# ClockRecovery.net
KiCad netlist of a schematic drawn in Altium Designer
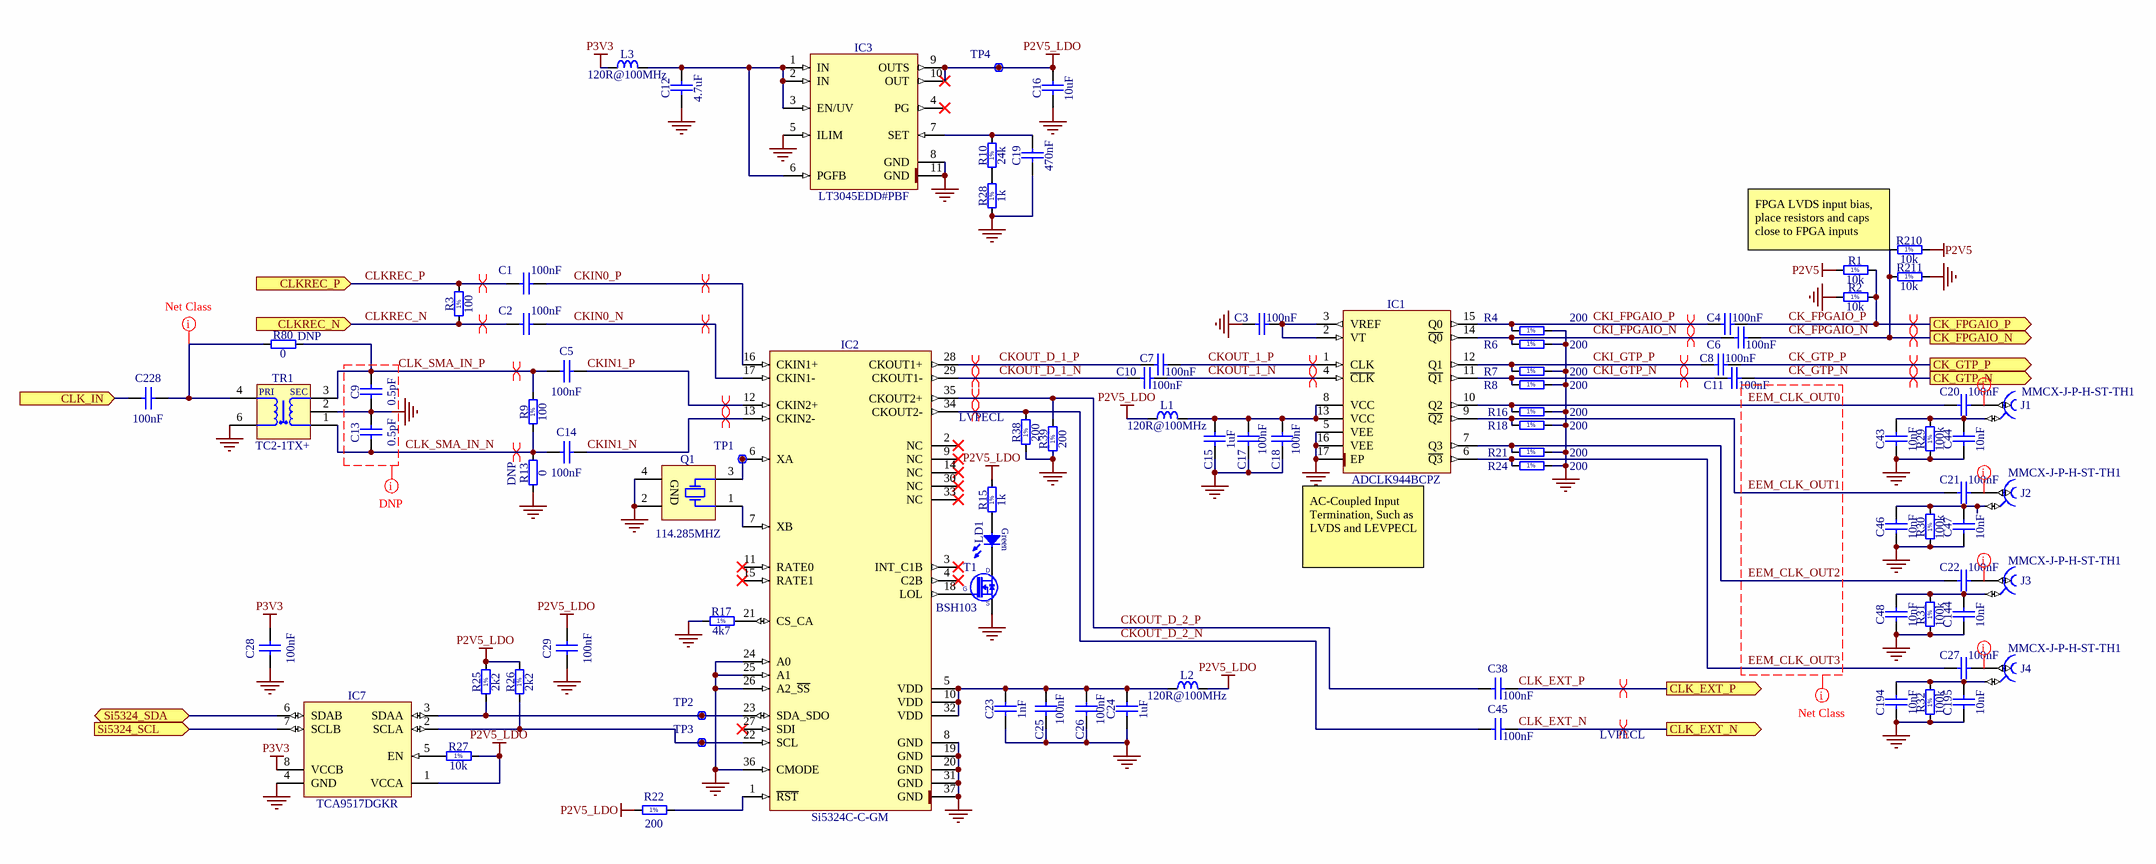
[diagram p0: ClockRecovery.SchDoc]

(export (version "E")
  (design (tool "Eeschema 10.0.6"))
  (components
    (comp (ref "C1")
      (value "100nF")
      (footprint "CAPC0603X33N")
      (description "Non-polarised capacitor")
      (fields
        (field (name "PART NUMBER") "CC0201_100NF_6.3V_10%_X5R")
        (field (name "VOLTAGE") "6.3V")
        (field (name "AUTHOR") "CERN DEM JLC")
      )
      (libsource (lib "Capacitors") (part "Capacitor - non polarized"))
    )
    (comp (ref "C2")
      (value "100nF")
      (footprint "CAPC0603X33N")
      (description "Non-polarised capacitor")
      (fields
        (field (name "PART NUMBER") "CC0201_100NF_6.3V_10%_X5R")
        (field (name "VOLTAGE") "6.3V")
        (field (name "AUTHOR") "CERN DEM JLC")
      )
      (libsource (lib "Capacitors") (part "Capacitor - non polarized"))
    )
    (comp (ref "C3")
      (value "100nF")
      (footprint "CAPC0603X33N")
      (description "Non-polarised capacitor")
      (fields
        (field (name "PART NUMBER") "CC0201_100NF_6.3V_10%_X5R")
        (field (name "VOLTAGE") "6.3V")
        (field (name "AUTHOR") "CERN DEM JLC")
      )
      (libsource (lib "Capacitors") (part "Capacitor - non polarized"))
    )
    (comp (ref "C4")
      (value "100nF")
      (footprint "CAPC0603X33N")
      (description "Non-polarised capacitor")
      (fields
        (field (name "PART NUMBER") "CC0201_100NF_6.3V_10%_X5R")
        (field (name "VOLTAGE") "6.3V")
        (field (name "AUTHOR") "CERN DEM JLC")
      )
      (libsource (lib "Capacitors") (part "Capacitor - non polarized"))
    )
    (comp (ref "C5")
      (value "100nF")
      (footprint "CAPC0603X33N")
      (description "Non-polarised capacitor")
      (fields
        (field (name "PART NUMBER") "CC0201_100NF_6.3V_10%_X5R")
        (field (name "VOLTAGE") "6.3V")
        (field (name "AUTHOR") "CERN DEM JLC")
      )
      (libsource (lib "Capacitors") (part "Capacitor - non polarized"))
    )
    (comp (ref "C6")
      (value "100nF")
      (footprint "CAPC0603X33N")
      (description "Non-polarised capacitor")
      (fields
        (field (name "PART NUMBER") "CC0201_100NF_6.3V_10%_X5R")
        (field (name "VOLTAGE") "6.3V")
        (field (name "AUTHOR") "CERN DEM JLC")
      )
      (libsource (lib "Capacitors") (part "Capacitor - non polarized"))
    )
    (comp (ref "C7")
      (value "100nF")
      (footprint "CAPC0603X33N")
      (description "Non-polarised capacitor")
      (fields
        (field (name "PART NUMBER") "CC0201_100NF_6.3V_10%_X5R")
        (field (name "VOLTAGE") "6.3V")
        (field (name "AUTHOR") "CERN DEM JLC")
      )
      (libsource (lib "Capacitors") (part "Capacitor - non polarized"))
    )
    (comp (ref "C8")
      (value "100nF")
      (footprint "CAPC0603X33N")
      (description "Non-polarised capacitor")
      (fields
        (field (name "PART NUMBER") "CC0201_100NF_6.3V_10%_X5R")
        (field (name "VOLTAGE") "6.3V")
        (field (name "AUTHOR") "CERN DEM JLC")
      )
      (libsource (lib "Capacitors") (part "Capacitor - non polarized"))
    )
    (comp (ref "C9")
      (value "0.5pF")
      (footprint "CAPC1005X50N")
      (description "Non-polarised capacitor")
      (fields
        (field (name "PART NUMBER") "CC0402_0.5PF_25V_0.05PF_AVX_04023J0R5ABSTR")
        (field (name "VOLTAGE") "25V")
        (field (name "AUTHOR") "CERN DEM JLC")
      )
      (libsource (lib "Capacitors") (part "Capacitor - non polarized"))
    )
    (comp (ref "C10")
      (value "100nF")
      (footprint "CAPC0603X33N")
      (description "Non-polarised capacitor")
      (fields
        (field (name "PART NUMBER") "CC0201_100NF_6.3V_10%_X5R")
        (field (name "VOLTAGE") "6.3V")
        (field (name "AUTHOR") "CERN DEM JLC")
      )
      (libsource (lib "Capacitors") (part "Capacitor - non polarized"))
    )
    (comp (ref "C11")
      (value "100nF")
      (footprint "CAPC0603X33N")
      (description "Non-polarised capacitor")
      (fields
        (field (name "PART NUMBER") "CC0201_100NF_6.3V_10%_X5R")
        (field (name "VOLTAGE") "6.3V")
        (field (name "AUTHOR") "CERN DEM JLC")
      )
      (libsource (lib "Capacitors") (part "Capacitor - non polarized"))
    )
    (comp (ref "C12")
      (value "4.7uF")
      (footprint "CAPC1005X55N")
      (description "Non-polarised capacitor")
      (fields
        (field (name "PART NUMBER") "CC0402_4.7UF_6.3V_20%_X5R")
        (field (name "VOLTAGE") "6.3V")
        (field (name "AUTHOR") "CERN DEM JLC")
      )
      (libsource (lib "Capacitors") (part "Capacitor - non polarized"))
    )
    (comp (ref "C13")
      (value "0.5pF")
      (footprint "CAPC1005X50N")
      (description "Non-polarised capacitor")
      (fields
        (field (name "PART NUMBER") "CC0402_0.5PF_25V_0.05PF_AVX_04023J0R5ABSTR")
        (field (name "VOLTAGE") "25V")
        (field (name "AUTHOR") "CERN DEM JLC")
      )
      (libsource (lib "Capacitors") (part "Capacitor - non polarized"))
    )
    (comp (ref "C14")
      (value "100nF")
      (footprint "CAPC0603X33N")
      (description "Non-polarised capacitor")
      (fields
        (field (name "PART NUMBER") "CC0201_100NF_6.3V_10%_X5R")
        (field (name "VOLTAGE") "6.3V")
        (field (name "AUTHOR") "CERN DEM JLC")
      )
      (libsource (lib "Capacitors") (part "Capacitor - non polarized"))
    )
    (comp (ref "C15")
      (value "1uF")
      (footprint "CAPC1005X55N")
      (description "Non-polarised capacitor")
      (fields
        (field (name "PART NUMBER") "CC0402_1UF_16V_10%_X5R")
        (field (name "VOLTAGE") "16V")
        (field (name "AUTHOR") "CERN DEM JLC")
      )
      (libsource (lib "Capacitors") (part "Capacitor - non polarized"))
    )
    (comp (ref "C16")
      (value "10uF")
      (footprint "CAPC1005X70N")
      (description "Non-polarised capacitor")
      (fields
        (field (name "PART NUMBER") "CC0402_10UF_6.3V_20%_X5R")
        (field (name "VOLTAGE") "6.3V")
        (field (name "AUTHOR") "CERN DEM JLC")
      )
      (libsource (lib "Capacitors") (part "Capacitor - non polarized"))
    )
    (comp (ref "C17")
      (value "100nF")
      (footprint "CAPC0603X33N")
      (description "Non-polarised capacitor")
      (fields
        (field (name "PART NUMBER") "CC0201_100NF_6.3V_10%_X5R")
        (field (name "VOLTAGE") "6.3V")
        (field (name "AUTHOR") "CERN DEM JLC")
      )
      (libsource (lib "Capacitors") (part "Capacitor - non polarized"))
    )
    (comp (ref "C18")
      (value "100nF")
      (footprint "CAPC0603X33N")
      (description "Non-polarised capacitor")
      (fields
        (field (name "PART NUMBER") "CC0201_100NF_6.3V_10%_X5R")
        (field (name "VOLTAGE") "6.3V")
        (field (name "AUTHOR") "CERN DEM JLC")
      )
      (libsource (lib "Capacitors") (part "Capacitor - non polarized"))
    )
    (comp (ref "C19")
      (value "470nF")
      (footprint "CAPC1005X55N")
      (description "Non-polarised capacitor")
      (fields
        (field (name "PART NUMBER") "CC0402_470NF_6.3V_10%_X5R")
        (field (name "VOLTAGE") "6.3V")
        (field (name "AUTHOR") "CERN DEM JLC")
      )
      (libsource (lib "Capacitors") (part "Capacitor - non polarized"))
    )
    (comp (ref "C20")
      (value "100nF")
      (footprint "CAPC0603X33N")
      (description "Non-polarised capacitor")
      (fields
        (field (name "PART NUMBER") "CC0201_100NF_6.3V_10%_X5R")
        (field (name "VOLTAGE") "6.3V")
        (field (name "AUTHOR") "CERN DEM JLC")
      )
      (libsource (lib "Capacitors") (part "Capacitor - non polarized"))
    )
    (comp (ref "C21")
      (value "100nF")
      (footprint "CAPC0603X33N")
      (description "Non-polarised capacitor")
      (fields
        (field (name "PART NUMBER") "CC0201_100NF_6.3V_10%_X5R")
        (field (name "VOLTAGE") "6.3V")
        (field (name "AUTHOR") "CERN DEM JLC")
      )
      (libsource (lib "Capacitors") (part "Capacitor - non polarized"))
    )
    (comp (ref "C22")
      (value "100nF")
      (footprint "CAPC0603X33N")
      (description "Non-polarised capacitor")
      (fields
        (field (name "PART NUMBER") "CC0201_100NF_6.3V_10%_X5R")
        (field (name "VOLTAGE") "6.3V")
        (field (name "AUTHOR") "CERN DEM JLC")
      )
      (libsource (lib "Capacitors") (part "Capacitor - non polarized"))
    )
    (comp (ref "C23")
      (value "1nF")
      (footprint "CAPC1005X55N")
      (description "Non-polarised capacitor")
      (fields
        (field (name "PART NUMBER") "CC0402_1NF_50V_10%_X7R")
        (field (name "VOLTAGE") "50V")
        (field (name "AUTHOR") "CERN DEM JLC")
      )
      (libsource (lib "Capacitors") (part "Capacitor - non polarized"))
    )
    (comp (ref "C24")
      (value "1uF")
      (footprint "CAPC1005X55N")
      (description "Non-polarised capacitor")
      (fields
        (field (name "PART NUMBER") "CC0402_1UF_16V_10%_X5R")
        (field (name "VOLTAGE") "16V")
        (field (name "AUTHOR") "CERN DEM JLC")
      )
      (libsource (lib "Capacitors") (part "Capacitor - non polarized"))
    )
    (comp (ref "C25")
      (value "100nF")
      (footprint "CAPC0603X33N")
      (description "Non-polarised capacitor")
      (fields
        (field (name "PART NUMBER") "CC0201_100NF_6.3V_10%_X5R")
        (field (name "VOLTAGE") "6.3V")
        (field (name "AUTHOR") "CERN DEM JLC")
      )
      (libsource (lib "Capacitors") (part "Capacitor - non polarized"))
    )
    (comp (ref "C26")
      (value "100nF")
      (footprint "CAPC0603X33N")
      (description "Non-polarised capacitor")
      (fields
        (field (name "PART NUMBER") "CC0201_100NF_6.3V_10%_X5R")
        (field (name "VOLTAGE") "6.3V")
        (field (name "AUTHOR") "CERN DEM JLC")
      )
      (libsource (lib "Capacitors") (part "Capacitor - non polarized"))
    )
    (comp (ref "C27")
      (value "100nF")
      (footprint "CAPC0603X33N")
      (description "Non-polarised capacitor")
      (fields
        (field (name "PART NUMBER") "CC0201_100NF_6.3V_10%_X5R")
        (field (name "VOLTAGE") "6.3V")
        (field (name "AUTHOR") "CERN DEM JLC")
      )
      (libsource (lib "Capacitors") (part "Capacitor - non polarized"))
    )
    (comp (ref "C28")
      (value "100nF")
      (footprint "CAPC0603X33N")
      (description "Non-polarised capacitor")
      (fields
        (field (name "PART NUMBER") "CC0201_100NF_6.3V_10%_X5R")
        (field (name "VOLTAGE") "6.3V")
        (field (name "AUTHOR") "CERN DEM JLC")
      )
      (libsource (lib "Capacitors") (part "Capacitor - non polarized"))
    )
    (comp (ref "C29")
      (value "100nF")
      (footprint "CAPC0603X33N")
      (description "Non-polarised capacitor")
      (fields
        (field (name "PART NUMBER") "CC0201_100NF_6.3V_10%_X5R")
        (field (name "VOLTAGE") "6.3V")
        (field (name "AUTHOR") "CERN DEM JLC")
      )
      (libsource (lib "Capacitors") (part "Capacitor - non polarized"))
    )
    (comp (ref "C38")
      (value "100nF")
      (footprint "CAPC0603X33N")
      (description "Non-polarised capacitor")
      (fields
        (field (name "PART NUMBER") "CC0201_100NF_6.3V_10%_X5R")
        (field (name "VOLTAGE") "6.3V")
        (field (name "AUTHOR") "CERN DEM JLC")
      )
      (libsource (lib "Capacitors") (part "Capacitor - non polarized"))
    )
    (comp (ref "C43")
      (value "10nF")
      (footprint "CAPC1005X55N")
      (description "Non-polarised capacitor")
      (fields
        (field (name "PART NUMBER") "CC0402_10NF_16V_10%_X7R")
        (field (name "VOLTAGE") "16V")
        (field (name "AUTHOR") "CERN DEM JLC")
      )
      (libsource (lib "Capacitors") (part "Capacitor - non polarized"))
    )
    (comp (ref "C44")
      (value "10nF")
      (footprint "CAPC1005X55N")
      (description "Non-polarised capacitor")
      (fields
        (field (name "PART NUMBER") "CC0402_10NF_16V_10%_X7R")
        (field (name "VOLTAGE") "16V")
        (field (name "AUTHOR") "CERN DEM JLC")
      )
      (libsource (lib "Capacitors") (part "Capacitor - non polarized"))
    )
    (comp (ref "C45")
      (value "100nF")
      (footprint "CAPC0603X33N")
      (description "Non-polarised capacitor")
      (fields
        (field (name "PART NUMBER") "CC0201_100NF_6.3V_10%_X5R")
        (field (name "VOLTAGE") "6.3V")
        (field (name "AUTHOR") "CERN DEM JLC")
      )
      (libsource (lib "Capacitors") (part "Capacitor - non polarized"))
    )
    (comp (ref "C46")
      (value "10nF")
      (footprint "CAPC1005X55N")
      (description "Non-polarised capacitor")
      (fields
        (field (name "PART NUMBER") "CC0402_10NF_16V_10%_X7R")
        (field (name "VOLTAGE") "16V")
        (field (name "AUTHOR") "CERN DEM JLC")
      )
      (libsource (lib "Capacitors") (part "Capacitor - non polarized"))
    )
    (comp (ref "C47")
      (value "10nF")
      (footprint "CAPC1005X55N")
      (description "Non-polarised capacitor")
      (fields
        (field (name "PART NUMBER") "CC0402_10NF_16V_10%_X7R")
        (field (name "VOLTAGE") "16V")
        (field (name "AUTHOR") "CERN DEM JLC")
      )
      (libsource (lib "Capacitors") (part "Capacitor - non polarized"))
    )
    (comp (ref "C48")
      (value "10nF")
      (footprint "CAPC1005X55N")
      (description "Non-polarised capacitor")
      (fields
        (field (name "PART NUMBER") "CC0402_10NF_16V_10%_X7R")
        (field (name "VOLTAGE") "16V")
        (field (name "AUTHOR") "CERN DEM JLC")
      )
      (libsource (lib "Capacitors") (part "Capacitor - non polarized"))
    )
    (comp (ref "C144")
      (value "10nF")
      (footprint "CAPC1005X55N")
      (description "Non-polarised capacitor")
      (fields
        (field (name "PART NUMBER") "CC0402_10NF_16V_10%_X7R")
        (field (name "VOLTAGE") "16V")
        (field (name "AUTHOR") "CERN DEM JLC")
      )
      (libsource (lib "Capacitors") (part "Capacitor - non polarized"))
    )
    (comp (ref "C194")
      (value "10nF")
      (footprint "CAPC1005X55N")
      (description "Non-polarised capacitor")
      (fields
        (field (name "PART NUMBER") "CC0402_10NF_16V_10%_X7R")
        (field (name "VOLTAGE") "16V")
        (field (name "AUTHOR") "CERN DEM JLC")
      )
      (libsource (lib "Capacitors") (part "Capacitor - non polarized"))
    )
    (comp (ref "C195")
      (value "10nF")
      (footprint "CAPC1005X55N")
      (description "Non-polarised capacitor")
      (fields
        (field (name "PART NUMBER") "CC0402_10NF_16V_10%_X7R")
        (field (name "VOLTAGE") "16V")
        (field (name "AUTHOR") "CERN DEM JLC")
      )
      (libsource (lib "Capacitors") (part "Capacitor - non polarized"))
    )
    (comp (ref "C228")
      (value "100nF")
      (footprint "CAPC0603X33N")
      (description "Non-polarised capacitor")
      (fields
        (field (name "PART NUMBER") "CC0201_100NF_6.3V_10%_X5R")
        (field (name "VOLTAGE") "6.3V")
        (field (name "AUTHOR") "CERN DEM JLC")
      )
      (libsource (lib "Capacitors") (part "Capacitor - non polarized"))
    )
    (comp (ref "IC1")
      (value "ADCLK944BCPZ")
      (footprint "QFN50P300X300X80-17N-S160")
      (description "2.5V/3.3V, Four LVPECL Outputs, SiGe Clock Fanout Buffer")
      (fields (field (name "MANUFACTURER") "ANALOG DEVICES") (field (name "AUTHOR") "CERN DEM JLC"))
      (libsource (lib "ICs And Semiconductors") (part "ADCLK944"))
    )
    (comp (ref "IC2")
      (value "Si5324C-C-GM")
      (footprint "QFN50P600X600X90-37N-S425")
      (description "Any Frequency Precision Clock Multiplier/Jitter Attenuator")
      (fields (field (name "MANUFACTURER") "SILICON LABS") (field (name "AUTHOR") "CERN DEM JLC"))
      (libsource (lib "ICs And Semiconductors") (part "Si5324"))
    )
    (comp (ref "IC3")
      (value "LT3045EDD#PBF")
      (footprint "SON50P300X300X80-11N-R175X248")
      (description "20V, 500mA, Ultralow Noise, Ultrahigh PSRR Linear Regulator")
      (fields (field (name "MANUFACTURER") "LINEAR TECHNOLOGY") (field (name "AUTHOR") "CERN DEM JLC"))
      (libsource (lib "ICs And Semiconductors") (part "LT3045EDD"))
    )
    (comp (ref "IC7")
      (value "TCA9517DGKR")
      (footprint "SOP65P490X110-8N")
      (description "Level-Translating I2C Bus Repeater")
      (fields (field (name "MANUFACTURER") "TEXAS INSTRUMENTS") (field (name "AUTHOR") "CERN DEM JLC"))
      (libsource (lib "ICs And Semiconductors") (part "TCA9517"))
    )
    (comp (ref "J1")
      (value "MMCX-J-P-H-ST-TH1")
      (footprint "SAMTEC_MMCX-J-P-H-ST-TH1")
      (fields
        (field (name "PART NUMBER") "SAMTEC_MMCX-J-P-H-ST-TH1")
        (field (name "MANUFACTURER") "SAMTEC")
        (field (name "AUTHOR") "CERN DEM JLC")
      )
      (libsource (lib "Connectors") (part "Coax_1Female_1Shield"))
    )
    (comp (ref "J2")
      (value "MMCX-J-P-H-ST-TH1")
      (footprint "SAMTEC_MMCX-J-P-H-ST-TH1")
      (fields
        (field (name "PART NUMBER") "SAMTEC_MMCX-J-P-H-ST-TH1")
        (field (name "MANUFACTURER") "SAMTEC")
        (field (name "AUTHOR") "CERN DEM JLC")
      )
      (libsource (lib "Connectors") (part "Coax_1Female_1Shield"))
    )
    (comp (ref "J3")
      (value "MMCX-J-P-H-ST-TH1")
      (footprint "SAMTEC_MMCX-J-P-H-ST-TH1")
      (fields
        (field (name "PART NUMBER") "SAMTEC_MMCX-J-P-H-ST-TH1")
        (field (name "MANUFACTURER") "SAMTEC")
        (field (name "AUTHOR") "CERN DEM JLC")
      )
      (libsource (lib "Connectors") (part "Coax_1Female_1Shield"))
    )
    (comp (ref "J4")
      (value "MMCX-J-P-H-ST-TH1")
      (footprint "SAMTEC_MMCX-J-P-H-ST-TH1")
      (fields
        (field (name "PART NUMBER") "SAMTEC_MMCX-J-P-H-ST-TH1")
        (field (name "MANUFACTURER") "SAMTEC")
        (field (name "AUTHOR") "CERN DEM JLC")
      )
      (libsource (lib "Connectors") (part "Coax_1Female_1Shield"))
    )
    (comp (ref "L1")
      (value "120R@100MHz")
      (footprint "INDC1608X65N")
      (description "Inductor")
      (fields
        (field (name "PART NUMBER") "IND0603_MURATA_BLM18SG121TN1D")
        (field (name "POWER") "3A")
        (field (name "AUTHOR") "CERN DEM JLC")
      )
      (libsource (lib "Inductors & Transformers") (part "Inductor"))
    )
    (comp (ref "L2")
      (value "120R@100MHz")
      (footprint "INDC1608X65N")
      (description "Inductor")
      (fields
        (field (name "PART NUMBER") "IND0603_MURATA_BLM18SG121TN1D")
        (field (name "POWER") "3A")
        (field (name "AUTHOR") "CERN DEM JLC")
      )
      (libsource (lib "") (part "Inductor_1"))
    )
    (comp (ref "L3")
      (value "120R@100MHz")
      (footprint "INDC1608X65N")
      (description "Inductor")
      (fields
        (field (name "PART NUMBER") "IND0603_MURATA_BLM18SG121TN1D")
        (field (name "POWER") "3A")
        (field (name "AUTHOR") "CERN DEM JLC")
      )
      (libsource (lib "") (part "Inductor_1"))
    )
    (comp (ref "LD1")
      (value "~")
      (footprint "LED_KINGBRIGHT_KPH-1608CGCK")
      (description "LED Green 1A 2C")
      (fields (field (name "MANUFACTURER PART NUMBER") "KPH-1608CGCK"))
      (libsource (lib "Schlib1") (part "KINGBRIGHT_KPTR-3216CGCK"))
    )
    (comp (ref "Q1")
      (value "114.285MHZ")
      (footprint "XTAL_CONNOR_CS")
      (description "Crystal 4 pins 1=XTAL Control 2=GND3=XTAL 4=GND")
      (fields
        (field (name "PART NUMBER") "XTAL_114.285MHZ_CONNOR_CS-023")
        (field (name "MANUFACTURER") "CONNOR-WINFIELD")
        (field (name "AUTHOR") "CERN DEM JLC")
      )
      (libsource (lib "ICs And Semiconductors") (part "Quartz Crystal 1X 2GND 3X 4GND"))
    )
    (comp (ref "R1")
      (value "10k")
      (footprint "RESC1005X40N")
      (description "Resistor - 1%")
      (fields
        (field (name "PART NUMBER") "R0402_10K_1%_0.0625W_100PPM")
        (field (name "POWER") "0.0625W")
        (field (name "AUTHOR") "CERN DEM JLC")
      )
      (libsource (lib "Resistors") (part "Resistor - 1%"))
    )
    (comp (ref "R2")
      (value "10k")
      (footprint "RESC1005X40N")
      (description "Resistor - 1%")
      (fields
        (field (name "PART NUMBER") "R0402_10K_1%_0.0625W_100PPM")
        (field (name "POWER") "0.0625W")
        (field (name "AUTHOR") "CERN DEM JLC")
      )
      (libsource (lib "Resistors") (part "Resistor - 1%"))
    )
    (comp (ref "R3")
      (value "100")
      (footprint "RESC1005X40N")
      (description "Resistor - 1%")
      (fields
        (field (name "PART NUMBER") "R0402_100R_1%_0.0625W_100PPM")
        (field (name "POWER") "0.0625W")
        (field (name "AUTHOR") "CERN DEM JLC")
      )
      (libsource (lib "Resistors") (part "Resistor - 1%"))
    )
    (comp (ref "R4")
      (value "200")
      (footprint "RESC1005X40N")
      (description "Resistor - 1%")
      (fields
        (field (name "PART NUMBER") "R0402_200R_1%_0.0625W_100PPM")
        (field (name "POWER") "0.0625W")
        (field (name "AUTHOR") "CERN DEM JLC")
      )
      (libsource (lib "Resistors") (part "Resistor - 1%"))
    )
    (comp (ref "R6")
      (value "200")
      (footprint "RESC1005X40N")
      (description "Resistor - 1%")
      (fields
        (field (name "PART NUMBER") "R0402_200R_1%_0.0625W_100PPM")
        (field (name "POWER") "0.0625W")
        (field (name "AUTHOR") "CERN DEM JLC")
      )
      (libsource (lib "Resistors") (part "Resistor - 1%"))
    )
    (comp (ref "R7")
      (value "200")
      (footprint "RESC1005X40N")
      (description "Resistor - 1%")
      (fields
        (field (name "PART NUMBER") "R0402_200R_1%_0.0625W_100PPM")
        (field (name "POWER") "0.0625W")
        (field (name "AUTHOR") "CERN DEM JLC")
      )
      (libsource (lib "Resistors") (part "Resistor - 1%"))
    )
    (comp (ref "R8")
      (value "200")
      (footprint "RESC1005X40N")
      (description "Resistor - 1%")
      (fields
        (field (name "PART NUMBER") "R0402_200R_1%_0.0625W_100PPM")
        (field (name "POWER") "0.0625W")
        (field (name "AUTHOR") "CERN DEM JLC")
      )
      (libsource (lib "Resistors") (part "Resistor - 1%"))
    )
    (comp (ref "R9")
      (value "100")
      (footprint "RESC1005X40N")
      (description "Resistor - 1%")
      (fields
        (field (name "PART NUMBER") "R0402_100R_1%_0.0625W_100PPM")
        (field (name "POWER") "0.0625W")
        (field (name "AUTHOR") "CERN DEM JLC")
      )
      (libsource (lib "Resistors") (part "Resistor - 1%"))
    )
    (comp (ref "R10")
      (value "24k")
      (footprint "RESC1005X40N")
      (description "Resistor - 1%")
      (fields
        (field (name "PART NUMBER") "R0402_24K_1%_0.0625W_100PPM")
        (field (name "POWER") "0.0625W")
        (field (name "AUTHOR") "CERN DEM JLC")
      )
      (libsource (lib "Resistors") (part "Resistor - 1%"))
    )
    (comp (ref "R13")
      (value "0")
      (footprint "RESC1005X40N")
      (description "Resistor")
      (fields
        (field (name "PART NUMBER") "R0402_0R_JUMPER")
        (field (name "MANUFACTURER") "GENERIC")
        (field (name "AUTHOR") "CERN DEM JLC")
      )
      (libsource (lib "Resistors") (part "Resistor"))
    )
    (comp (ref "R15")
      (value "1k")
      (footprint "RESC1005X40N")
      (description "Resistor - 1%")
      (fields
        (field (name "PART NUMBER") "R0402_1K_1%_0.0625W_100PPM")
        (field (name "POWER") "0.0625W")
        (field (name "AUTHOR") "CERN DEM JLC")
      )
      (libsource (lib "Resistors") (part "Resistor - 1%"))
    )
    (comp (ref "R16")
      (value "200")
      (footprint "RESC1005X40N")
      (description "Resistor - 1%")
      (fields
        (field (name "PART NUMBER") "R0402_200R_1%_0.0625W_100PPM")
        (field (name "POWER") "0.0625W")
        (field (name "AUTHOR") "CERN DEM JLC")
      )
      (libsource (lib "Resistors") (part "Resistor - 1%"))
    )
    (comp (ref "R17")
      (value "4k7")
      (footprint "RESC1005X40N")
      (description "Resistor - 1%")
      (fields
        (field (name "PART NUMBER") "R0402_4K7_1%_0.0625W_100PPM")
        (field (name "POWER") "0.0625W")
        (field (name "AUTHOR") "CERN DEM JLC")
      )
      (libsource (lib "Resistors") (part "Resistor - 1%"))
    )
    (comp (ref "R18")
      (value "200")
      (footprint "RESC1005X40N")
      (description "Resistor - 1%")
      (fields
        (field (name "PART NUMBER") "R0402_200R_1%_0.0625W_100PPM")
        (field (name "POWER") "0.0625W")
        (field (name "AUTHOR") "CERN DEM JLC")
      )
      (libsource (lib "Resistors") (part "Resistor - 1%"))
    )
    (comp (ref "R21")
      (value "200")
      (footprint "RESC1005X40N")
      (description "Resistor - 1%")
      (fields
        (field (name "PART NUMBER") "R0402_200R_1%_0.0625W_100PPM")
        (field (name "POWER") "0.0625W")
        (field (name "AUTHOR") "CERN DEM JLC")
      )
      (libsource (lib "Resistors") (part "Resistor - 1%"))
    )
    (comp (ref "R22")
      (value "200")
      (footprint "RESC1005X40N")
      (description "Resistor - 1%")
      (fields
        (field (name "PART NUMBER") "R0402_200R_1%_0.0625W_100PPM")
        (field (name "POWER") "0.0625W")
        (field (name "AUTHOR") "CERN DEM JLC")
      )
      (libsource (lib "Resistors") (part "Resistor - 1%"))
    )
    (comp (ref "R24")
      (value "200")
      (footprint "RESC1005X40N")
      (description "Resistor - 1%")
      (fields
        (field (name "PART NUMBER") "R0402_200R_1%_0.0625W_100PPM")
        (field (name "POWER") "0.0625W")
        (field (name "AUTHOR") "CERN DEM JLC")
      )
      (libsource (lib "Resistors") (part "Resistor - 1%"))
    )
    (comp (ref "R25")
      (value "2k2")
      (footprint "RESC1005X40N")
      (description "Resistor - 1%")
      (fields
        (field (name "PART NUMBER") "R0402_2K2_1%_0.0625W_100PPM")
        (field (name "POWER") "0.0625W")
        (field (name "AUTHOR") "CERN DEM JLC")
      )
      (libsource (lib "Resistors") (part "Resistor - 1%"))
    )
    (comp (ref "R26")
      (value "2k2")
      (footprint "RESC1005X40N")
      (description "Resistor - 1%")
      (fields
        (field (name "PART NUMBER") "R0402_2K2_1%_0.0625W_100PPM")
        (field (name "POWER") "0.0625W")
        (field (name "AUTHOR") "CERN DEM JLC")
      )
      (libsource (lib "Resistors") (part "Resistor - 1%"))
    )
    (comp (ref "R27")
      (value "10k")
      (footprint "RESC1005X40N")
      (description "Resistor - 1%")
      (fields
        (field (name "PART NUMBER") "R0402_10K_1%_0.0625W_100PPM")
        (field (name "POWER") "0.0625W")
        (field (name "AUTHOR") "CERN DEM JLC")
      )
      (libsource (lib "Resistors") (part "Resistor - 1%"))
    )
    (comp (ref "R28")
      (value "1k")
      (footprint "RESC1005X40N")
      (description "Resistor - 1%")
      (fields
        (field (name "PART NUMBER") "R0402_1K_1%_0.0625W_100PPM")
        (field (name "POWER") "0.0625W")
        (field (name "AUTHOR") "CERN DEM JLC")
      )
      (libsource (lib "Resistors") (part "Resistor - 1%"))
    )
    (comp (ref "R29")
      (value "100k")
      (footprint "RESC1005X40N")
      (description "Resistor - 1%")
      (fields
        (field (name "PART NUMBER") "R0402_100K_1%_0.0625W_100PPM")
        (field (name "MANUFACTURER") "GENERIC")
        (field (name "AUTHOR") "CERN DEM JLC")
      )
      (libsource (lib "Resistors") (part "Resistor - 1%"))
    )
    (comp (ref "R30")
      (value "100k")
      (footprint "RESC1005X40N")
      (description "Resistor - 1%")
      (fields
        (field (name "PART NUMBER") "R0402_100K_1%_0.0625W_100PPM")
        (field (name "MANUFACTURER") "GENERIC")
        (field (name "AUTHOR") "CERN DEM JLC")
      )
      (libsource (lib "Resistors") (part "Resistor - 1%"))
    )
    (comp (ref "R31")
      (value "100k")
      (footprint "RESC1005X40N")
      (description "Resistor - 1%")
      (fields
        (field (name "PART NUMBER") "R0402_100K_1%_0.0625W_100PPM")
        (field (name "MANUFACTURER") "GENERIC")
        (field (name "AUTHOR") "CERN DEM JLC")
      )
      (libsource (lib "Resistors") (part "Resistor - 1%"))
    )
    (comp (ref "R32")
      (value "100k")
      (footprint "RESC1005X40N")
      (description "Resistor - 1%")
      (fields
        (field (name "PART NUMBER") "R0402_100K_1%_0.0625W_100PPM")
        (field (name "MANUFACTURER") "GENERIC")
        (field (name "AUTHOR") "CERN DEM JLC")
      )
      (libsource (lib "Resistors") (part "Resistor - 1%"))
    )
    (comp (ref "R38")
      (value "200")
      (footprint "RESC1005X40N")
      (description "Resistor - 1%")
      (fields
        (field (name "PART NUMBER") "R0402_200R_1%_0.0625W_100PPM")
        (field (name "POWER") "0.0625W")
        (field (name "AUTHOR") "CERN DEM JLC")
      )
      (libsource (lib "Resistors") (part "Resistor - 1%"))
    )
    (comp (ref "R39")
      (value "200")
      (footprint "RESC1005X40N")
      (description "Resistor - 1%")
      (fields
        (field (name "PART NUMBER") "R0402_200R_1%_0.0625W_100PPM")
        (field (name "POWER") "0.0625W")
        (field (name "AUTHOR") "CERN DEM JLC")
      )
      (libsource (lib "Resistors") (part "Resistor - 1%"))
    )
    (comp (ref "R80")
      (value "0")
      (footprint "RESC1005X40N")
      (description "Resistor")
      (fields
        (field (name "PART NUMBER") "R0402_0R_JUMPER")
        (field (name "MANUFACTURER") "GENERIC")
        (field (name "AUTHOR") "CERN DEM JLC")
      )
      (libsource (lib "Resistors") (part "Resistor"))
    )
    (comp (ref "R210")
      (value "10k")
      (footprint "RESC1005X40N")
      (description "Resistor - 1%")
      (fields
        (field (name "PART NUMBER") "R0402_10K_1%_0.0625W_100PPM")
        (field (name "POWER") "0.0625W")
        (field (name "AUTHOR") "CERN DEM JLC")
      )
      (libsource (lib "Resistors") (part "Resistor - 1%"))
    )
    (comp (ref "R211")
      (value "10k")
      (footprint "RESC1005X40N")
      (description "Resistor - 1%")
      (fields
        (field (name "PART NUMBER") "R0402_10K_1%_0.0625W_100PPM")
        (field (name "POWER") "0.0625W")
        (field (name "AUTHOR") "CERN DEM JLC")
      )
      (libsource (lib "Resistors") (part "Resistor - 1%"))
    )
    (comp (ref "T1")
      (value "BSH103")
      (footprint "SOT95P230X110-3N")
      (description "N-CHANNEL MOSFET WITH DIODE")
      (fields (field (name "MANUFACTURER") "NEXPERIA") (field (name "AUTHOR") "CERN DEM JLC"))
      (libsource (lib "ICs And Semiconductors") (part "N-MOSFET-D 1G 2S 3D"))
    )
    (comp (ref "TP1")
      (value "Q1")
      (footprint "TPS127")
      (description "Test Point")
      (fields (field (name "PART NUMBER") "SMD_PAD_1.27X1.27MM") (field (name "AUTHOR") "CERN DEM JLC"))
      (libsource (lib "Eletro-mechanical") (part "Test Point"))
    )
    (comp (ref "TP2")
      (value "Si5324 I2C SDA")
      (footprint "TPS127")
      (description "Test Point")
      (fields (field (name "PART NUMBER") "SMD_PAD_1.27X1.27MM") (field (name "AUTHOR") "CERN DEM JLC"))
      (libsource (lib "Eletro-mechanical") (part "Test Point"))
    )
    (comp (ref "TP3")
      (value "Si5324 I2C SCL")
      (footprint "TPS127")
      (description "Test Point")
      (fields (field (name "PART NUMBER") "SMD_PAD_1.27X1.27MM") (field (name "AUTHOR") "CERN DEM JLC"))
      (libsource (lib "Eletro-mechanical") (part "Test Point"))
    )
    (comp (ref "TP4")
      (value "P2V5 LDO")
      (footprint "TPS127")
      (description "Test Point")
      (fields (field (name "PART NUMBER") "SMD_PAD_1.27X1.27MM") (field (name "AUTHOR") "CERN DEM JLC"))
      (libsource (lib "Eletro-mechanical") (part "Test Point"))
    )
    (comp (ref "TR1")
      (value "TC2-1TX+")
      (footprint "XFMR_MINI-CIRCUITS_AT1521")
      (description "50 Ohm 3 to 300MHz RF Transformers")
      (fields (field (name "MANUFACTURER") "MINI-CIRCUITS"))
      (libsource (lib "Schlib1") (part "XFMR_MINI-CIRCUITS_TC2-1TX+"))
    )
  )
  (nets
    (net (code "1") (name "/CKIN0_N") (class "Default")
      (node (ref "C2") (pin "2") (pinfunction "2_2") (pintype "passive"))
      (node (ref "IC2") (pin "17") (pinfunction "CKIN1-_17") (pintype "input"))
    )
    (net (code "2") (name "/CKIN0_P") (class "Default")
      (node (ref "C1") (pin "2") (pinfunction "2_2") (pintype "passive"))
      (node (ref "IC2") (pin "16") (pinfunction "CKIN1+_16") (pintype "input"))
    )
    (net (code "3") (name "/CKIN1_N") (class "Default")
      (node (ref "C14") (pin "2") (pinfunction "2_2") (pintype "passive"))
      (node (ref "IC2") (pin "13") (pinfunction "CKIN2-_13") (pintype "input"))
    )
    (net (code "4") (name "/CKIN1_P") (class "Default")
      (node (ref "C5") (pin "2") (pinfunction "2_2") (pintype "passive"))
      (node (ref "IC2") (pin "12") (pinfunction "CKIN2+_12") (pintype "input"))
    )
    (net (code "5") (name "/CKI_FPGAIO_N") (class "Default")
      (node (ref "C6") (pin "1") (pinfunction "1_1") (pintype "passive"))
      (node (ref "IC1") (pin "14") (pinfunction "~{Q0}_14") (pintype "output"))
      (node (ref "R6") (pin "1") (pinfunction "1_1") (pintype "passive"))
    )
    (net (code "6") (name "/CKI_FPGAIO_P") (class "Default")
      (node (ref "C4") (pin "1") (pinfunction "1_1") (pintype "passive"))
      (node (ref "IC1") (pin "15") (pinfunction "Q0_15") (pintype "output"))
      (node (ref "R4") (pin "1") (pinfunction "1_1") (pintype "passive"))
    )
    (net (code "7") (name "/CKI_GTP_N") (class "Default")
      (node (ref "C11") (pin "1") (pinfunction "1_1") (pintype "passive"))
      (node (ref "IC1") (pin "11") (pinfunction "~{Q1}_11") (pintype "output"))
      (node (ref "R8") (pin "1") (pinfunction "1_1") (pintype "passive"))
    )
    (net (code "8") (name "/CKI_GTP_P") (class "Default")
      (node (ref "C8") (pin "1") (pinfunction "1_1") (pintype "passive"))
      (node (ref "IC1") (pin "12") (pinfunction "Q1_12") (pintype "output"))
      (node (ref "R7") (pin "1") (pinfunction "1_1") (pintype "passive"))
    )
    (net (code "9") (name "/CKOUT_1_N") (class "Default")
      (node (ref "C10") (pin "2") (pinfunction "2_2") (pintype "passive"))
      (node (ref "IC1") (pin "4") (pinfunction "~{CLK}_4") (pintype "input"))
    )
    (net (code "10") (name "/CKOUT_1_P") (class "Default")
      (node (ref "C7") (pin "2") (pinfunction "2_2") (pintype "passive"))
      (node (ref "IC1") (pin "1") (pinfunction "CLK_1") (pintype "input"))
    )
    (net (code "11") (name "/CKOUT_D_1_N") (class "Default")
      (node (ref "C10") (pin "1") (pinfunction "1_1") (pintype "passive"))
      (node (ref "IC2") (pin "29") (pinfunction "CKOUT1-_29") (pintype "output"))
    )
    (net (code "12") (name "/CKOUT_D_1_P") (class "Default")
      (node (ref "C7") (pin "1") (pinfunction "1_1") (pintype "passive"))
      (node (ref "IC2") (pin "28") (pinfunction "CKOUT1+_28") (pintype "output"))
    )
    (net (code "13") (name "/CKOUT_D_2_N") (class "Default")
      (node (ref "C45") (pin "1") (pinfunction "1_1") (pintype "passive"))
      (node (ref "IC2") (pin "34") (pinfunction "CKOUT2-_34") (pintype "output"))
      (node (ref "R38") (pin "2") (pinfunction "2_2") (pintype "passive"))
    )
    (net (code "14") (name "/CKOUT_D_2_P") (class "Default")
      (node (ref "C38") (pin "1") (pinfunction "1_1") (pintype "passive"))
      (node (ref "IC2") (pin "35") (pinfunction "CKOUT2+_35") (pintype "output"))
      (node (ref "R39") (pin "2") (pinfunction "2_2") (pintype "passive"))
    )
    (net (code "15") (name "/CK_FPGAIO_N") (class "Default")
      (node (ref "C6") (pin "2") (pinfunction "2_2") (pintype "passive"))
      (node (ref "R210") (pin "2") (pinfunction "2_2") (pintype "passive"))
      (node (ref "R211") (pin "2") (pinfunction "2_2") (pintype "passive"))
    )
    (net (code "16") (name "/CK_FPGAIO_P") (class "Default")
      (node (ref "C4") (pin "2") (pinfunction "2_2") (pintype "passive"))
      (node (ref "R1") (pin "2") (pinfunction "2_2") (pintype "passive"))
      (node (ref "R2") (pin "2") (pinfunction "2_2") (pintype "passive"))
    )
    (net (code "17") (name "/CK_GTP_N") (class "Default")
      (node (ref "C11") (pin "2") (pinfunction "2_2") (pintype "passive"))
    )
    (net (code "18") (name "/CK_GTP_P") (class "Default")
      (node (ref "C8") (pin "2") (pinfunction "2_2") (pintype "passive"))
    )
    (net (code "19") (name "/CLKREC_N") (class "Default")
      (node (ref "C2") (pin "1") (pinfunction "1_1") (pintype "passive"))
      (node (ref "R3") (pin "1") (pinfunction "1_1") (pintype "passive"))
    )
    (net (code "20") (name "/CLKREC_P") (class "Default")
      (node (ref "C1") (pin "1") (pinfunction "1_1") (pintype "passive"))
      (node (ref "R3") (pin "2") (pinfunction "2_2") (pintype "passive"))
    )
    (net (code "21") (name "/CLK_EXT_N") (class "Default")
      (node (ref "C45") (pin "2") (pinfunction "2_2") (pintype "passive"))
    )
    (net (code "22") (name "/CLK_EXT_P") (class "Default")
      (node (ref "C38") (pin "2") (pinfunction "2_2") (pintype "passive"))
    )
    (net (code "23") (name "/CLK_IN") (class "Default")
      (node (ref "C228") (pin "1") (pinfunction "1_1") (pintype "passive"))
    )
    (net (code "24") (name "/CLK_SMA_IN_N") (class "Default")
      (node (ref "C13") (pin "1") (pinfunction "1_1") (pintype "passive"))
      (node (ref "C14") (pin "1") (pinfunction "1_1") (pintype "passive"))
      (node (ref "R13") (pin "2") (pinfunction "2_2") (pintype "passive"))
      (node (ref "R9") (pin "1") (pinfunction "1_1") (pintype "passive"))
      (node (ref "TR1") (pin "1") (pinfunction "SDOT_1") (pintype "passive"))
    )
    (net (code "25") (name "/CLK_SMA_IN_P") (class "Default")
      (node (ref "C5") (pin "1") (pinfunction "1_1") (pintype "passive"))
      (node (ref "C9") (pin "2") (pinfunction "2_2") (pintype "passive"))
      (node (ref "R80") (pin "2") (pinfunction "2_2") (pintype "passive"))
      (node (ref "R9") (pin "2") (pinfunction "2_2") (pintype "passive"))
      (node (ref "TR1") (pin "3") (pinfunction "S_3") (pintype "passive"))
    )
    (net (code "26") (name "/EEM_CLK_OUT0") (class "Default")
      (node (ref "C20") (pin "1") (pinfunction "1_1") (pintype "passive"))
      (node (ref "IC1") (pin "10") (pinfunction "Q2_10") (pintype "output"))
      (node (ref "R16") (pin "1") (pinfunction "1_1") (pintype "passive"))
    )
    (net (code "27") (name "/EEM_CLK_OUT1") (class "Default")
      (node (ref "C21") (pin "1") (pinfunction "1_1") (pintype "passive"))
      (node (ref "IC1") (pin "9") (pinfunction "~{Q2}_9") (pintype "output"))
      (node (ref "R18") (pin "1") (pinfunction "1_1") (pintype "passive"))
    )
    (net (code "28") (name "/EEM_CLK_OUT2") (class "Default")
      (node (ref "C22") (pin "1") (pinfunction "1_1") (pintype "passive"))
      (node (ref "IC1") (pin "7") (pinfunction "Q3_7") (pintype "output"))
      (node (ref "R21") (pin "1") (pinfunction "1_1") (pintype "passive"))
    )
    (net (code "29") (name "/EEM_CLK_OUT3") (class "Default")
      (node (ref "C27") (pin "1") (pinfunction "1_1") (pintype "passive"))
      (node (ref "IC1") (pin "6") (pinfunction "~{Q3}_6") (pintype "output"))
      (node (ref "R24") (pin "1") (pinfunction "1_1") (pintype "passive"))
    )
    (net (code "30") (name "/Si5324_SCL") (class "Default")
      (node (ref "IC7") (pin "7") (pinfunction "SCLB_7") (pintype "bidirectional"))
    )
    (net (code "31") (name "/Si5324_SDA") (class "Default")
      (node (ref "IC7") (pin "6") (pinfunction "SDAB_6") (pintype "bidirectional"))
    )
    (net (code "32") (name "GND") (class "Default")
      (node (ref "C12") (pin "1") (pinfunction "1_1") (pintype "passive"))
      (node (ref "C13") (pin "2") (pinfunction "2_2") (pintype "passive"))
      (node (ref "C144") (pin "1") (pinfunction "1_1") (pintype "passive"))
      (node (ref "C15") (pin "1") (pinfunction "1_1") (pintype "passive"))
      (node (ref "C16") (pin "1") (pinfunction "1_1") (pintype "passive"))
      (node (ref "C17") (pin "1") (pinfunction "1_1") (pintype "passive"))
      (node (ref "C18") (pin "1") (pinfunction "1_1") (pintype "passive"))
      (node (ref "C19") (pin "1") (pinfunction "1_1") (pintype "passive"))
      (node (ref "C194") (pin "1") (pinfunction "1_1") (pintype "passive"))
      (node (ref "C195") (pin "1") (pinfunction "1_1") (pintype "passive"))
      (node (ref "C23") (pin "1") (pinfunction "1_1") (pintype "passive"))
      (node (ref "C24") (pin "1") (pinfunction "1_1") (pintype "passive"))
      (node (ref "C25") (pin "1") (pinfunction "1_1") (pintype "passive"))
      (node (ref "C26") (pin "1") (pinfunction "1_1") (pintype "passive"))
      (node (ref "C28") (pin "1") (pinfunction "1_1") (pintype "passive"))
      (node (ref "C29") (pin "1") (pinfunction "1_1") (pintype "passive"))
      (node (ref "C3") (pin "1") (pinfunction "1_1") (pintype "passive"))
      (node (ref "C43") (pin "1") (pinfunction "1_1") (pintype "passive"))
      (node (ref "C44") (pin "1") (pinfunction "1_1") (pintype "passive"))
      (node (ref "C46") (pin "1") (pinfunction "1_1") (pintype "passive"))
      (node (ref "C47") (pin "1") (pinfunction "1_1") (pintype "passive"))
      (node (ref "C48") (pin "1") (pinfunction "1_1") (pintype "passive"))
      (node (ref "C9") (pin "1") (pinfunction "1_1") (pintype "passive"))
      (node (ref "IC1") (pin "16") (pinfunction "VEE_16") (pintype "power_in"))
      (node (ref "IC1") (pin "17") (pinfunction "EP_17") (pintype "power_in"))
      (node (ref "IC1") (pin "5") (pinfunction "VEE_5") (pintype "power_in"))
      (node (ref "IC2") (pin "19") (pinfunction "GND_19") (pintype "power_in"))
      (node (ref "IC2") (pin "20") (pinfunction "GND_20") (pintype "power_in"))
      (node (ref "IC2") (pin "24") (pinfunction "A0_24") (pintype "input"))
      (node (ref "IC2") (pin "25") (pinfunction "A1_25") (pintype "input"))
      (node (ref "IC2") (pin "26") (pinfunction "A2_~{SS}_26") (pintype "input"))
      (node (ref "IC2") (pin "31") (pinfunction "GND_31") (pintype "power_in"))
      (node (ref "IC2") (pin "36") (pinfunction "CMODE_36") (pintype "input"))
      (node (ref "IC2") (pin "37") (pinfunction "GND_37") (pintype "power_in"))
      (node (ref "IC2") (pin "8") (pinfunction "GND_8") (pintype "power_in"))
      (node (ref "IC3") (pin "11") (pinfunction "GND_11") (pintype "power_in"))
      (node (ref "IC3") (pin "5") (pinfunction "ILIM_5") (pintype "input"))
      (node (ref "IC3") (pin "8") (pinfunction "GND_8") (pintype "power_in"))
      (node (ref "IC7") (pin "4") (pinfunction "GND_4") (pintype "power_in"))
      (node (ref "Q1") (pin "2") (pinfunction "GND_2") (pintype "power_in"))
      (node (ref "Q1") (pin "4") (pinfunction "GND_4") (pintype "power_in"))
      (node (ref "R13") (pin "1") (pinfunction "1_1") (pintype "passive"))
      (node (ref "R16") (pin "2") (pinfunction "2_2") (pintype "passive"))
      (node (ref "R17") (pin "1") (pinfunction "1_1") (pintype "passive"))
      (node (ref "R18") (pin "2") (pinfunction "2_2") (pintype "passive"))
      (node (ref "R2") (pin "1") (pinfunction "1_1") (pintype "passive"))
      (node (ref "R21") (pin "2") (pinfunction "2_2") (pintype "passive"))
      (node (ref "R211") (pin "1") (pinfunction "1_1") (pintype "passive"))
      (node (ref "R24") (pin "2") (pinfunction "2_2") (pintype "passive"))
      (node (ref "R28") (pin "1") (pinfunction "1_1") (pintype "passive"))
      (node (ref "R29") (pin "1") (pinfunction "1_1") (pintype "passive"))
      (node (ref "R30") (pin "1") (pinfunction "1_1") (pintype "passive"))
      (node (ref "R31") (pin "1") (pinfunction "1_1") (pintype "passive"))
      (node (ref "R32") (pin "1") (pinfunction "1_1") (pintype "passive"))
      (node (ref "R38") (pin "1") (pinfunction "1_1") (pintype "passive"))
      (node (ref "R39") (pin "1") (pinfunction "1_1") (pintype "passive"))
      (node (ref "R4") (pin "2") (pinfunction "2_2") (pintype "passive"))
      (node (ref "R6") (pin "2") (pinfunction "2_2") (pintype "passive"))
      (node (ref "R7") (pin "2") (pinfunction "2_2") (pintype "passive"))
      (node (ref "R8") (pin "2") (pinfunction "2_2") (pintype "passive"))
      (node (ref "T1") (pin "2") (pinfunction "S_2") (pintype "passive"))
      (node (ref "TR1") (pin "2") (pinfunction "NU_2") (pintype "passive"))
      (node (ref "TR1") (pin "6") (pinfunction "PDOT_6") (pintype "passive"))
    )
    (net (code "33") (name "Net-(C15-Pad2)") (class "Default")
      (node (ref "C15") (pin "2") (pinfunction "2_2") (pintype "passive"))
      (node (ref "C17") (pin "2") (pinfunction "2_2") (pintype "passive"))
      (node (ref "C18") (pin "2") (pinfunction "2_2") (pintype "passive"))
      (node (ref "IC1") (pin "13") (pinfunction "VCC_13") (pintype "power_in"))
      (node (ref "IC1") (pin "8") (pinfunction "VCC_8") (pintype "power_in"))
      (node (ref "L1") (pin "1") (pinfunction "1_1") (pintype "passive"))
    )
    (net (code "34") (name "Net-(C20-Pad2)") (class "Default")
      (node (ref "C20") (pin "2") (pinfunction "2_2") (pintype "passive"))
      (node (ref "J1") (pin "1") (pinfunction "1_1") (pintype "bidirectional"))
    )
    (net (code "35") (name "Net-(C21-Pad2)") (class "Default")
      (node (ref "C21") (pin "2") (pinfunction "2_2") (pintype "passive"))
      (node (ref "J2") (pin "1") (pinfunction "1_1") (pintype "bidirectional"))
    )
    (net (code "36") (name "Net-(C22-Pad2)") (class "Default")
      (node (ref "C22") (pin "2") (pinfunction "2_2") (pintype "passive"))
      (node (ref "J3") (pin "1") (pinfunction "1_1") (pintype "bidirectional"))
    )
    (net (code "37") (name "Net-(C23-Pad2)") (class "Default")
      (node (ref "C23") (pin "2") (pinfunction "2_2") (pintype "passive"))
      (node (ref "C24") (pin "2") (pinfunction "2_2") (pintype "passive"))
      (node (ref "C25") (pin "2") (pinfunction "2_2") (pintype "passive"))
      (node (ref "C26") (pin "2") (pinfunction "2_2") (pintype "passive"))
      (node (ref "IC2") (pin "10") (pinfunction "VDD_10") (pintype "power_in"))
      (node (ref "IC2") (pin "32") (pinfunction "VDD_32") (pintype "power_in"))
      (node (ref "IC2") (pin "5") (pinfunction "VDD_5") (pintype "power_in"))
      (node (ref "L2") (pin "1") (pinfunction "1_1") (pintype "passive"))
    )
    (net (code "38") (name "Net-(C27-Pad2)") (class "Default")
      (node (ref "C27") (pin "2") (pinfunction "2_2") (pintype "passive"))
      (node (ref "J4") (pin "1") (pinfunction "1_1") (pintype "bidirectional"))
    )
    (net (code "39") (name "Net-(C43-Pad2)") (class "Default")
      (node (ref "C43") (pin "2") (pinfunction "2_2") (pintype "passive"))
      (node (ref "C44") (pin "2") (pinfunction "2_2") (pintype "passive"))
      (node (ref "J1") (pin "2") (pinfunction "2_2") (pintype "bidirectional"))
      (node (ref "R29") (pin "2") (pinfunction "2_2") (pintype "passive"))
    )
    (net (code "40") (name "Net-(C46-Pad2)") (class "Default")
      (node (ref "C46") (pin "2") (pinfunction "2_2") (pintype "passive"))
      (node (ref "C47") (pin "2") (pinfunction "2_2") (pintype "passive"))
      (node (ref "J2") (pin "2") (pinfunction "2_2") (pintype "bidirectional"))
      (node (ref "R30") (pin "2") (pinfunction "2_2") (pintype "passive"))
    )
    (net (code "41") (name "Net-(C144-Pad2)") (class "Default")
      (node (ref "C144") (pin "2") (pinfunction "2_2") (pintype "passive"))
      (node (ref "C48") (pin "2") (pinfunction "2_2") (pintype "passive"))
      (node (ref "J3") (pin "2") (pinfunction "2_2") (pintype "bidirectional"))
      (node (ref "R31") (pin "2") (pinfunction "2_2") (pintype "passive"))
    )
    (net (code "42") (name "Net-(C194-Pad2)") (class "Default")
      (node (ref "C194") (pin "2") (pinfunction "2_2") (pintype "passive"))
      (node (ref "C195") (pin "2") (pinfunction "2_2") (pintype "passive"))
      (node (ref "J4") (pin "2") (pinfunction "2_2") (pintype "bidirectional"))
      (node (ref "R32") (pin "2") (pinfunction "2_2") (pintype "passive"))
    )
    (net (code "43") (name "Net-(IC1-VREF)") (class "Default")
      (node (ref "C3") (pin "2") (pinfunction "2_2") (pintype "passive"))
      (node (ref "IC1") (pin "2") (pinfunction "VT_2") (pintype "input"))
      (node (ref "IC1") (pin "3") (pinfunction "VREF_3") (pintype "output"))
    )
    (net (code "44") (name "Net-(IC2-CS_CA)") (class "Default")
      (node (ref "IC2") (pin "21") (pinfunction "CS_CA_21") (pintype "bidirectional"))
      (node (ref "R17") (pin "2") (pinfunction "2_2") (pintype "passive"))
    )
    (net (code "45") (name "Net-(IC2-LOL)") (class "Default")
      (node (ref "IC2") (pin "18") (pinfunction "LOL_18") (pintype "output"))
      (node (ref "T1") (pin "1") (pinfunction "G_1") (pintype "passive"))
    )
    (net (code "46") (name "Net-(IC2-SCL)") (class "Default")
      (node (ref "IC2") (pin "22") (pinfunction "SCL_22") (pintype "input"))
      (node (ref "IC7") (pin "2") (pinfunction "SCLA_2") (pintype "bidirectional"))
      (node (ref "R26") (pin "1") (pinfunction "1_1") (pintype "passive"))
      (node (ref "TP3") (pin "1") (pinfunction "1_1") (pintype "bidirectional"))
    )
    (net (code "47") (name "Net-(IC2-SDA_SDO)") (class "Default")
      (node (ref "IC2") (pin "23") (pinfunction "SDA_SDO_23") (pintype "bidirectional"))
      (node (ref "IC7") (pin "3") (pinfunction "SDAA_3") (pintype "bidirectional"))
      (node (ref "R25") (pin "1") (pinfunction "1_1") (pintype "passive"))
      (node (ref "TP2") (pin "1") (pinfunction "1_1") (pintype "bidirectional"))
    )
    (net (code "48") (name "Net-(IC2-XA)") (class "Default")
      (node (ref "IC2") (pin "6") (pinfunction "XA_6") (pintype "input"))
      (node (ref "Q1") (pin "3") (pinfunction "X_3") (pintype "passive"))
      (node (ref "TP1") (pin "1") (pinfunction "1_1") (pintype "bidirectional"))
    )
    (net (code "49") (name "Net-(IC2-XB)") (class "Default")
      (node (ref "IC2") (pin "7") (pinfunction "XB_7") (pintype "input"))
      (node (ref "Q1") (pin "1") (pinfunction "X_1") (pintype "passive"))
    )
    (net (code "50") (name "Net-(IC2-~{RST})") (class "Default")
      (node (ref "IC2") (pin "1") (pinfunction "~{RST}_1") (pintype "input"))
      (node (ref "R22") (pin "2") (pinfunction "2_2") (pintype "passive"))
    )
    (net (code "51") (name "Net-(IC3-EN{slash}UV)") (class "Default")
      (node (ref "C12") (pin "2") (pinfunction "2_2") (pintype "passive"))
      (node (ref "IC3") (pin "1") (pinfunction "IN_1") (pintype "input"))
      (node (ref "IC3") (pin "2") (pinfunction "IN_2") (pintype "input"))
      (node (ref "IC3") (pin "3") (pinfunction "EN/UV_3") (pintype "input"))
      (node (ref "IC3") (pin "6") (pinfunction "PGFB_6") (pintype "input"))
      (node (ref "L3") (pin "2") (pinfunction "2_2") (pintype "passive"))
    )
    (net (code "52") (name "Net-(IC3-SET)") (class "Default")
      (node (ref "C19") (pin "2") (pinfunction "2_2") (pintype "passive"))
      (node (ref "IC3") (pin "7") (pinfunction "SET_7") (pintype "input"))
      (node (ref "R10") (pin "2") (pinfunction "2_2") (pintype "passive"))
    )
    (net (code "53") (name "Net-(IC7-EN)") (class "Default")
      (node (ref "IC7") (pin "5") (pinfunction "EN_5") (pintype "input"))
      (node (ref "R27") (pin "2") (pinfunction "2_2") (pintype "passive"))
    )
    (net (code "54") (name "Net-(LD1-A)") (class "Default")
      (node (ref "LD1") (pin "1") (pinfunction "A_1") (pintype "passive"))
      (node (ref "R15") (pin "1") (pinfunction "1_1") (pintype "passive"))
    )
    (net (code "55") (name "Net-(LD1-C)") (class "Default")
      (node (ref "LD1") (pin "2") (pinfunction "C_2") (pintype "passive"))
      (node (ref "T1") (pin "3") (pinfunction "D_3") (pintype "passive"))
    )
    (net (code "56") (name "Net-(R10-Pad1)") (class "Default")
      (node (ref "R10") (pin "1") (pinfunction "1_1") (pintype "passive"))
      (node (ref "R28") (pin "2") (pinfunction "2_2") (pintype "passive"))
    )
    (net (code "57") (name "Net-(TR1-P)") (class "Default")
      (node (ref "C228") (pin "2") (pinfunction "2_2") (pintype "passive"))
      (node (ref "R80") (pin "1") (pinfunction "1_1") (pintype "passive"))
      (node (ref "TR1") (pin "4") (pinfunction "P_4") (pintype "passive"))
    )
    (net (code "58") (name "P2V5") (class "Default")
      (node (ref "R1") (pin "1") (pinfunction "1_1") (pintype "passive"))
      (node (ref "R210") (pin "1") (pinfunction "1_1") (pintype "passive"))
    )
    (net (code "59") (name "P2V5_LDO") (class "Default")
      (node (ref "C16") (pin "2") (pinfunction "2_2") (pintype "passive"))
      (node (ref "C29") (pin "2") (pinfunction "2_2") (pintype "passive"))
      (node (ref "IC3") (pin "10") (pinfunction "OUT_10") (pintype "output"))
      (node (ref "IC3") (pin "9") (pinfunction "OUTS_9") (pintype "output"))
      (node (ref "IC7") (pin "1") (pinfunction "VCCA_1") (pintype "power_in"))
      (node (ref "L1") (pin "2") (pinfunction "2_2") (pintype "passive"))
      (node (ref "L2") (pin "2") (pinfunction "2_2") (pintype "passive"))
      (node (ref "R15") (pin "2") (pinfunction "2_2") (pintype "passive"))
      (node (ref "R22") (pin "1") (pinfunction "1_1") (pintype "passive"))
      (node (ref "R25") (pin "2") (pinfunction "2_2") (pintype "passive"))
      (node (ref "R26") (pin "2") (pinfunction "2_2") (pintype "passive"))
      (node (ref "R27") (pin "1") (pinfunction "1_1") (pintype "passive"))
      (node (ref "TP4") (pin "1") (pinfunction "1_1") (pintype "bidirectional"))
    )
    (net (code "60") (name "P3V3") (class "Default")
      (node (ref "C28") (pin "2") (pinfunction "2_2") (pintype "passive"))
      (node (ref "IC7") (pin "8") (pinfunction "VCCB_8") (pintype "power_in"))
      (node (ref "L3") (pin "1") (pinfunction "1_1") (pintype "passive"))
    )
    (net (code "61") (name "unconnected-(IC2-C2B-Pad4)") (class "Default")
      (node (ref "IC2") (pin "4") (pinfunction "C2B_4") (pintype "output+no_connect"))
    )
    (net (code "62") (name "unconnected-(IC2-INT_C1B-Pad3)") (class "Default")
      (node (ref "IC2") (pin "3") (pinfunction "INT_C1B_3") (pintype "output+no_connect"))
    )
    (net (code "63") (name "unconnected-(IC2-NC-Pad2)") (class "Default")
      (node (ref "IC2") (pin "2") (pinfunction "NC_2") (pintype "passive+no_connect"))
    )
    (net (code "64") (name "unconnected-(IC2-NC-Pad9)") (class "Default")
      (node (ref "IC2") (pin "9") (pinfunction "NC_9") (pintype "passive+no_connect"))
    )
    (net (code "65") (name "unconnected-(IC2-NC-Pad14)") (class "Default")
      (node (ref "IC2") (pin "14") (pinfunction "NC_14") (pintype "passive+no_connect"))
    )
    (net (code "66") (name "unconnected-(IC2-NC-Pad30)") (class "Default")
      (node (ref "IC2") (pin "30") (pinfunction "NC_30") (pintype "passive+no_connect"))
    )
    (net (code "67") (name "unconnected-(IC2-NC-Pad33)") (class "Default")
      (node (ref "IC2") (pin "33") (pinfunction "NC_33") (pintype "passive+no_connect"))
    )
    (net (code "68") (name "unconnected-(IC2-RATE0-Pad11)") (class "Default")
      (node (ref "IC2") (pin "11") (pinfunction "RATE0_11") (pintype "input+no_connect"))
    )
    (net (code "69") (name "unconnected-(IC2-RATE1-Pad15)") (class "Default")
      (node (ref "IC2") (pin "15") (pinfunction "RATE1_15") (pintype "input+no_connect"))
    )
    (net (code "70") (name "unconnected-(IC2-SDI-Pad27)") (class "Default")
      (node (ref "IC2") (pin "27") (pinfunction "SDI_27") (pintype "input+no_connect"))
    )
    (net (code "71") (name "unconnected-(IC3-PG-Pad4)") (class "Default")
      (node (ref "IC3") (pin "4") (pinfunction "PG_4") (pintype "output+no_connect"))
    )
  )
)
